# FPGA_board-v1.net
KiCad netlist of a schematic drawn in EAGLE
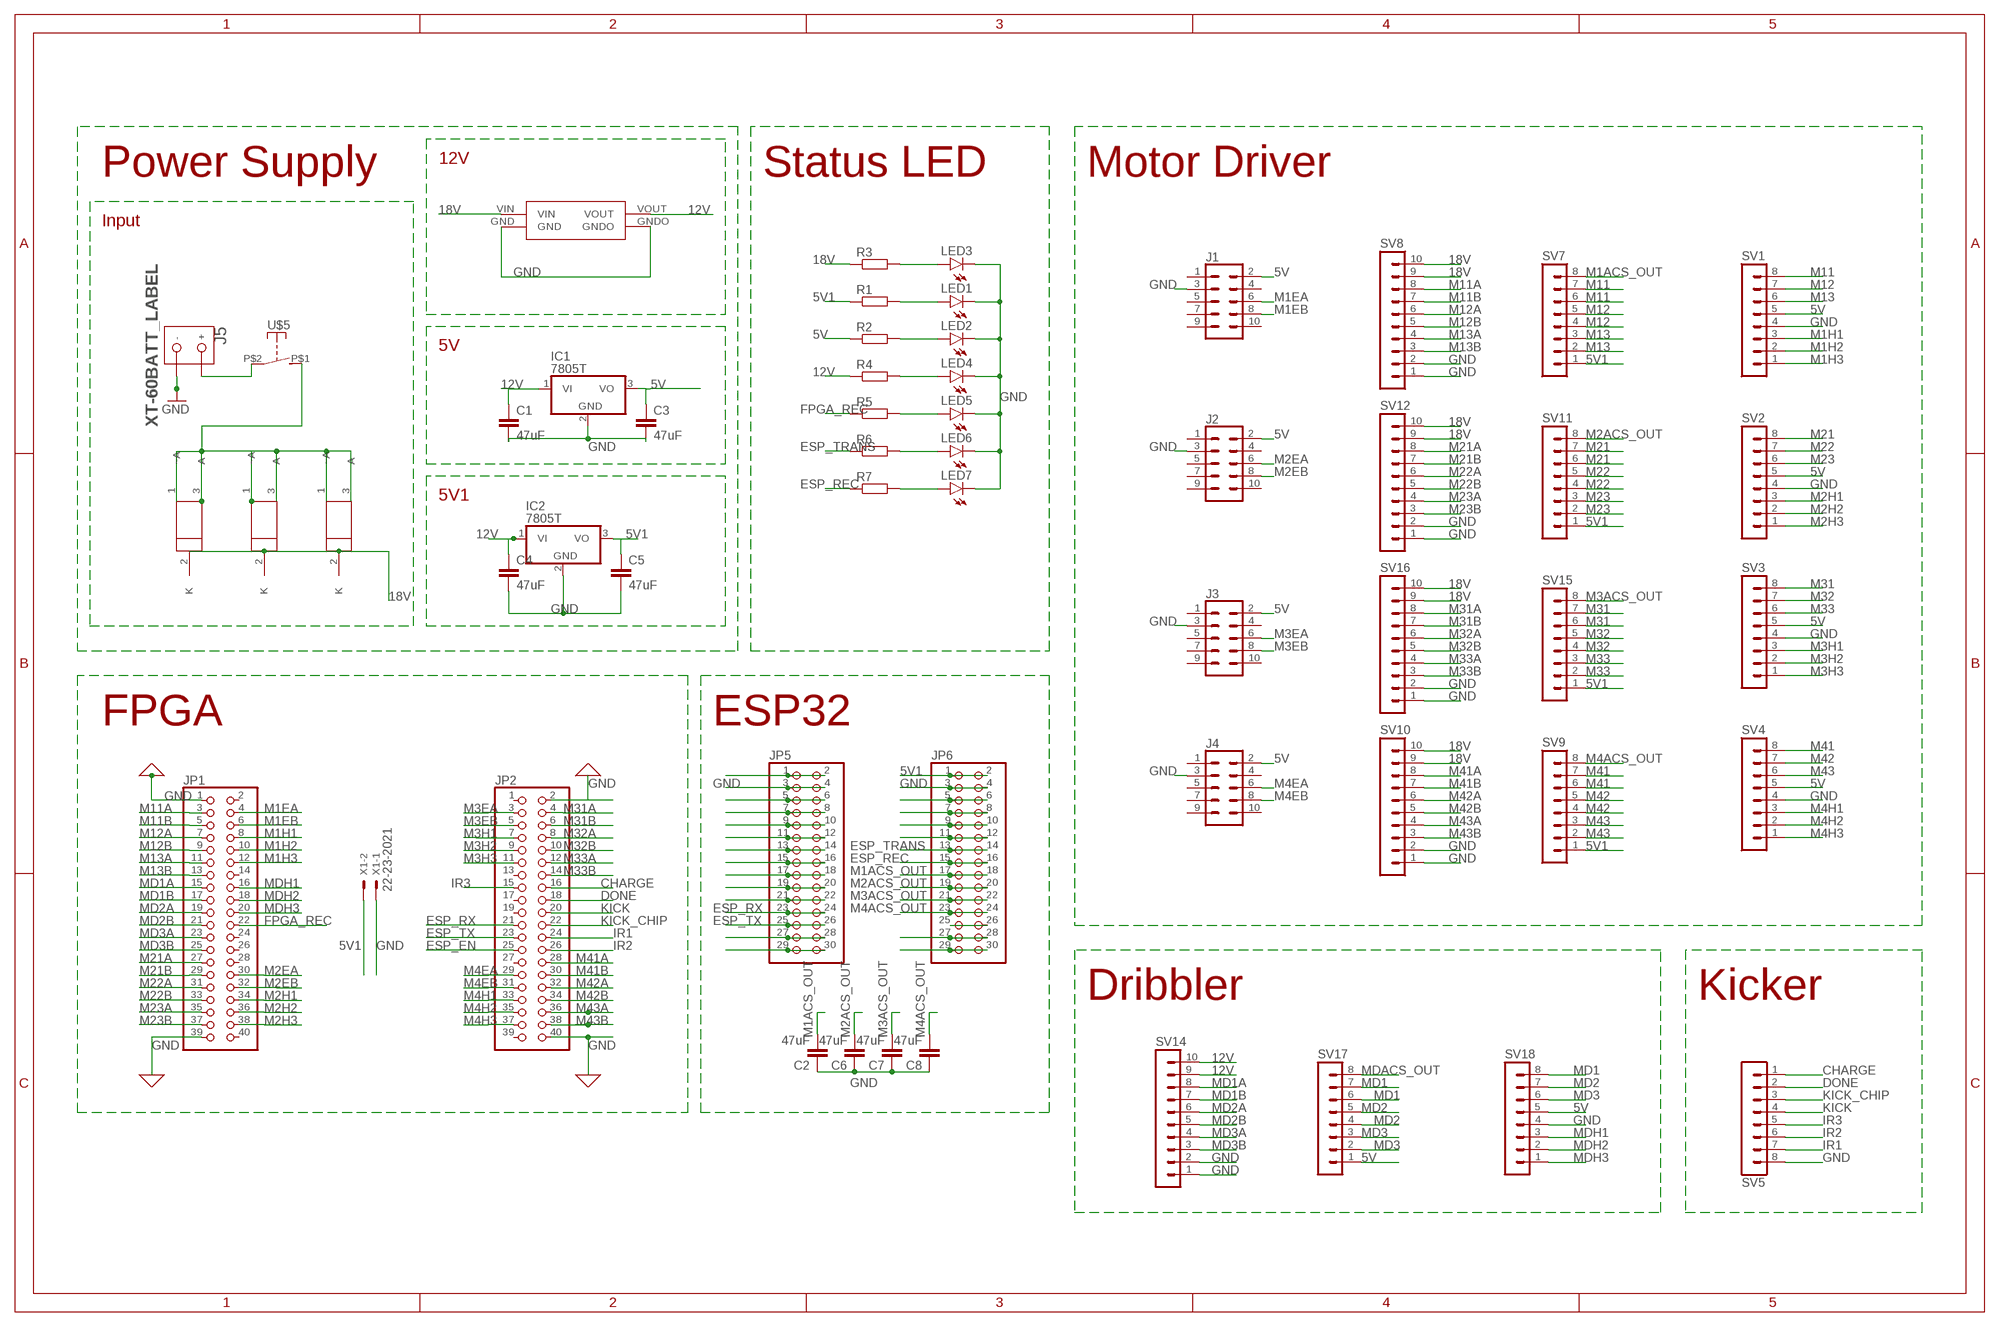
[diagram p0: schematic, sheet 1]

(export (version "E")
  (design (tool "Eeschema 10.0.6"))
  (components
    (comp (ref "C1")
      (value "47uF")
      (footprint "eagle-import:C1206")
      (libsource (lib "eagle-import") (part "C-EUC1206"))
    )
    (comp (ref "C2")
      (value "47uF")
      (footprint "eagle-import:C1206")
      (libsource (lib "eagle-import") (part "C-EUC1206"))
    )
    (comp (ref "C3")
      (value "47uF")
      (footprint "eagle-import:C1206")
      (libsource (lib "eagle-import") (part "C-EUC1206"))
    )
    (comp (ref "C4")
      (value "47uF")
      (footprint "eagle-import:C1206")
      (libsource (lib "eagle-import") (part "C-EUC1206"))
    )
    (comp (ref "C5")
      (value "47uF")
      (footprint "eagle-import:C1206")
      (libsource (lib "eagle-import") (part "C-EUC1206"))
    )
    (comp (ref "C6")
      (value "47uF")
      (footprint "eagle-import:C1206")
      (libsource (lib "eagle-import") (part "C-EUC1206"))
    )
    (comp (ref "C7")
      (value "47uF")
      (footprint "eagle-import:C1206")
      (libsource (lib "eagle-import") (part "C-EUC1206"))
    )
    (comp (ref "C8")
      (value "47uF")
      (footprint "eagle-import:C1206")
      (libsource (lib "eagle-import") (part "C-EUC1206"))
    )
    (comp (ref "IC1")
      (value "7805T")
      (footprint "eagle-import:TO220H")
      (libsource (lib "eagle-import") (part "78T05"))
    )
    (comp (ref "IC2")
      (value "7805T")
      (footprint "eagle-import:TO220H")
      (libsource (lib "eagle-import") (part "78T05"))
    )
    (comp (ref "J1")
      (value "CONN_05X2SHD_LOCK")
      (footprint "eagle-import:2X5-SHROUDED_LOCK")
      (libsource (lib "eagle-import") (part "CONN_05X2SHD_LOCK"))
    )
    (comp (ref "J2")
      (value "CONN_05X2SHD_LOCK")
      (footprint "eagle-import:2X5-SHROUDED_LOCK")
      (libsource (lib "eagle-import") (part "CONN_05X2SHD_LOCK"))
    )
    (comp (ref "J3")
      (value "CONN_05X2SHD_LOCK")
      (footprint "eagle-import:2X5-SHROUDED_LOCK")
      (libsource (lib "eagle-import") (part "CONN_05X2SHD_LOCK"))
    )
    (comp (ref "J4")
      (value "CONN_05X2SHD_LOCK")
      (footprint "eagle-import:2X5-SHROUDED_LOCK")
      (libsource (lib "eagle-import") (part "CONN_05X2SHD_LOCK"))
    )
    (comp (ref "J5")
      (value "XT-60BATT_LABEL")
      (footprint "eagle-import:XT-60")
      (libsource (lib "eagle-import") (part "XT-60BATT_LABEL"))
    )
    (comp (ref "JP1")
      (value "PINHD-2X20")
      (footprint "eagle-import:2X20")
      (libsource (lib "eagle-import") (part "PINHD-2X20"))
    )
    (comp (ref "JP2")
      (value "PINHD-2X20")
      (footprint "eagle-import:2X20")
      (libsource (lib "eagle-import") (part "PINHD-2X20"))
    )
    (comp (ref "JP5")
      (value "PINHD-2X15")
      (footprint "eagle-import:2X15")
      (libsource (lib "eagle-import") (part "PINHD-2X15"))
    )
    (comp (ref "JP6")
      (value "PINHD-2X15")
      (footprint "eagle-import:2X15")
      (libsource (lib "eagle-import") (part "PINHD-2X15"))
    )
    (comp (ref "LED1")
      (value "LEDSMT1206")
      (footprint "eagle-import:1206")
      (libsource (lib "eagle-import") (part "LEDSMT1206"))
    )
    (comp (ref "LED2")
      (value "LEDSMT1206")
      (footprint "eagle-import:1206")
      (libsource (lib "eagle-import") (part "LEDSMT1206"))
    )
    (comp (ref "LED3")
      (value "LEDSMT1206")
      (footprint "eagle-import:1206")
      (libsource (lib "eagle-import") (part "LEDSMT1206"))
    )
    (comp (ref "LED4")
      (value "LEDSMT1206")
      (footprint "eagle-import:1206")
      (libsource (lib "eagle-import") (part "LEDSMT1206"))
    )
    (comp (ref "LED5")
      (value "LEDSMT1206")
      (footprint "eagle-import:1206")
      (libsource (lib "eagle-import") (part "LEDSMT1206"))
    )
    (comp (ref "LED6")
      (value "LEDSMT1206")
      (footprint "eagle-import:1206")
      (libsource (lib "eagle-import") (part "LEDSMT1206"))
    )
    (comp (ref "LED7")
      (value "LEDSMT1206")
      (footprint "eagle-import:1206")
      (libsource (lib "eagle-import") (part "LEDSMT1206"))
    )
    (comp (ref "R1")
      (value "R-EU_R1206")
      (footprint "eagle-import:R1206")
      (libsource (lib "eagle-import") (part "R-EU_R1206"))
    )
    (comp (ref "R2")
      (value "R-EU_R1206")
      (footprint "eagle-import:R1206")
      (libsource (lib "eagle-import") (part "R-EU_R1206"))
    )
    (comp (ref "R3")
      (value "R-EU_R1206")
      (footprint "eagle-import:R1206")
      (libsource (lib "eagle-import") (part "R-EU_R1206"))
    )
    (comp (ref "R4")
      (value "R-EU_R1206")
      (footprint "eagle-import:R1206")
      (libsource (lib "eagle-import") (part "R-EU_R1206"))
    )
    (comp (ref "R5")
      (value "R-EU_R1206")
      (footprint "eagle-import:R1206")
      (libsource (lib "eagle-import") (part "R-EU_R1206"))
    )
    (comp (ref "R6")
      (value "R-EU_R1206")
      (footprint "eagle-import:R1206")
      (libsource (lib "eagle-import") (part "R-EU_R1206"))
    )
    (comp (ref "R7")
      (value "R-EU_R1206")
      (footprint "eagle-import:R1206")
      (libsource (lib "eagle-import") (part "R-EU_R1206"))
    )
    (comp (ref "SV1")
      (value "MA08-1")
      (footprint "eagle-import:MA08-1")
      (libsource (lib "eagle-import") (part "MA08-1"))
    )
    (comp (ref "SV2")
      (value "MA08-1")
      (footprint "eagle-import:MA08-1")
      (libsource (lib "eagle-import") (part "MA08-1"))
    )
    (comp (ref "SV3")
      (value "MA08-1")
      (footprint "eagle-import:MA08-1")
      (libsource (lib "eagle-import") (part "MA08-1"))
    )
    (comp (ref "SV4")
      (value "MA08-1")
      (footprint "eagle-import:MA08-1")
      (libsource (lib "eagle-import") (part "MA08-1"))
    )
    (comp (ref "SV5")
      (value "MA08-1")
      (footprint "eagle-import:MA08-1")
      (libsource (lib "eagle-import") (part "MA08-1"))
    )
    (comp (ref "SV7")
      (value "MA08-1")
      (footprint "eagle-import:MA08-1")
      (libsource (lib "eagle-import") (part "MA08-1"))
    )
    (comp (ref "SV8")
      (value "MA10-1")
      (footprint "eagle-import:MA10-1")
      (libsource (lib "eagle-import") (part "MA10-1"))
    )
    (comp (ref "SV9")
      (value "MA08-1")
      (footprint "eagle-import:MA08-1")
      (libsource (lib "eagle-import") (part "MA08-1"))
    )
    (comp (ref "SV10")
      (value "MA10-1")
      (footprint "eagle-import:MA10-1")
      (libsource (lib "eagle-import") (part "MA10-1"))
    )
    (comp (ref "SV11")
      (value "MA08-1")
      (footprint "eagle-import:MA08-1")
      (libsource (lib "eagle-import") (part "MA08-1"))
    )
    (comp (ref "SV12")
      (value "MA10-1")
      (footprint "eagle-import:MA10-1")
      (libsource (lib "eagle-import") (part "MA10-1"))
    )
    (comp (ref "SV14")
      (value "MA10-1")
      (footprint "eagle-import:MA10-1")
      (libsource (lib "eagle-import") (part "MA10-1"))
    )
    (comp (ref "SV15")
      (value "MA08-1")
      (footprint "eagle-import:MA08-1")
      (libsource (lib "eagle-import") (part "MA08-1"))
    )
    (comp (ref "SV16")
      (value "MA10-1")
      (footprint "eagle-import:MA10-1")
      (libsource (lib "eagle-import") (part "MA10-1"))
    )
    (comp (ref "SV17")
      (value "MA08-1")
      (footprint "eagle-import:MA08-1")
      (libsource (lib "eagle-import") (part "MA08-1"))
    )
    (comp (ref "SV18")
      (value "MA08-1")
      (footprint "eagle-import:MA08-1")
      (libsource (lib "eagle-import") (part "MA08-1"))
    )
    (comp (ref "U$4")
      (value "BUCK")
      (footprint "eagle-import:BUCK")
      (libsource (lib "eagle-import") (part "BUCK"))
    )
    (comp (ref "U$5")
      (value "SWITCH_DA10")
      (footprint "eagle-import:DA10")
      (libsource (lib "eagle-import") (part "SWITCH_DA10"))
    )
    (comp (ref "U1")
      (value "LP38690DT-3.3")
      (footprint "eagle-import:TO228P1042X238-3N")
      (libsource (lib "eagle-import") (part "LP38690DT-3.3"))
    )
    (comp (ref "U2")
      (value "LP38690DT-3.3")
      (footprint "eagle-import:TO228P1042X238-3N")
      (libsource (lib "eagle-import") (part "LP38690DT-3.3"))
    )
    (comp (ref "U3")
      (value "LP38690DT-3.3")
      (footprint "eagle-import:TO228P1042X238-3N")
      (libsource (lib "eagle-import") (part "LP38690DT-3.3"))
    )
    (comp (ref "X1")
      (value "22-23-2021")
      (footprint "eagle-import:22-23-2021")
      (fields (field (name "MF") "MOLEX"))
      (libsource (lib "eagle-import") (part "22-23-2021"))
    )
  )
  (nets
    (net (code "1") (name "/5V") (class "Default")
      (node (ref "C3") (pin "1") (pinfunction "1_1") (pintype "passive"))
      (node (ref "IC1") (pin "3") (pinfunction "VO_3") (pintype "passive"))
      (node (ref "J1") (pin "2") (pinfunction "2_2") (pintype "passive"))
      (node (ref "J2") (pin "2") (pinfunction "2_2") (pintype "passive"))
      (node (ref "J3") (pin "2") (pinfunction "2_2") (pintype "passive"))
      (node (ref "J4") (pin "2") (pinfunction "2_2") (pintype "passive"))
      (node (ref "R2") (pin "1") (pinfunction "1_1") (pintype "passive"))
      (node (ref "SV1") (pin "5") (pinfunction "5_5") (pintype "passive"))
      (node (ref "SV17") (pin "1") (pinfunction "1_1") (pintype "passive"))
      (node (ref "SV18") (pin "5") (pinfunction "5_5") (pintype "passive"))
      (node (ref "SV2") (pin "5") (pinfunction "5_5") (pintype "passive"))
      (node (ref "SV3") (pin "5") (pinfunction "5_5") (pintype "passive"))
      (node (ref "SV4") (pin "5") (pinfunction "5_5") (pintype "passive"))
    )
    (net (code "2") (name "/5V1") (class "Default")
      (node (ref "C5") (pin "1") (pinfunction "1_1") (pintype "passive"))
      (node (ref "IC2") (pin "3") (pinfunction "VO_3") (pintype "passive"))
      (node (ref "JP6") (pin "1") (pinfunction "1_1") (pintype "passive"))
      (node (ref "JP6") (pin "2") (pinfunction "2_2") (pintype "passive"))
      (node (ref "R1") (pin "1") (pinfunction "1_1") (pintype "passive"))
      (node (ref "SV11") (pin "1") (pinfunction "1_1") (pintype "passive"))
      (node (ref "SV15") (pin "1") (pinfunction "1_1") (pintype "passive"))
      (node (ref "SV7") (pin "1") (pinfunction "1_1") (pintype "passive"))
      (node (ref "SV9") (pin "1") (pinfunction "1_1") (pintype "passive"))
      (node (ref "X1") (pin "2") (pinfunction "S_2") (pintype "passive"))
    )
    (net (code "3") (name "/12V") (class "Default")
      (node (ref "C1") (pin "1") (pinfunction "1_1") (pintype "passive"))
      (node (ref "C4") (pin "1") (pinfunction "1_1") (pintype "passive"))
      (node (ref "IC1") (pin "1") (pinfunction "VI_1") (pintype "input"))
      (node (ref "IC2") (pin "1") (pinfunction "VI_1") (pintype "input"))
      (node (ref "R4") (pin "1") (pinfunction "1_1") (pintype "passive"))
      (node (ref "SV14") (pin "10") (pinfunction "10_10") (pintype "passive"))
      (node (ref "SV14") (pin "9") (pinfunction "9_9") (pintype "passive"))
      (node (ref "U$4") (pin "VOUT") (pinfunction "VOUT_VOUT") (pintype "bidirectional"))
    )
    (net (code "4") (name "/18V") (class "Default")
      (node (ref "R3") (pin "1") (pinfunction "1_1") (pintype "passive"))
      (node (ref "SV10") (pin "10") (pinfunction "10_10") (pintype "passive"))
      (node (ref "SV10") (pin "9") (pinfunction "9_9") (pintype "passive"))
      (node (ref "SV12") (pin "10") (pinfunction "10_10") (pintype "passive"))
      (node (ref "SV12") (pin "9") (pinfunction "9_9") (pintype "passive"))
      (node (ref "SV16") (pin "10") (pinfunction "10_10") (pintype "passive"))
      (node (ref "SV16") (pin "9") (pinfunction "9_9") (pintype "passive"))
      (node (ref "SV8") (pin "10") (pinfunction "10_10") (pintype "passive"))
      (node (ref "SV8") (pin "9") (pinfunction "9_9") (pintype "passive"))
      (node (ref "U$4") (pin "VIN") (pinfunction "VIN_VIN") (pintype "bidirectional"))
      (node (ref "U1") (pin "2") (pinfunction "K_2") (pintype "bidirectional"))
      (node (ref "U2") (pin "2") (pinfunction "K_2") (pintype "bidirectional"))
      (node (ref "U3") (pin "2") (pinfunction "K_2") (pintype "bidirectional"))
    )
    (net (code "5") (name "/CHARGE") (class "Default")
      (node (ref "JP2") (pin "16") (pinfunction "16_16") (pintype "passive"))
      (node (ref "SV5") (pin "1") (pinfunction "1_1") (pintype "passive"))
    )
    (net (code "6") (name "/DONE") (class "Default")
      (node (ref "JP2") (pin "18") (pinfunction "18_18") (pintype "passive"))
      (node (ref "SV5") (pin "2") (pinfunction "2_2") (pintype "passive"))
    )
    (net (code "7") (name "/ESP_EN") (class "Default")
      (node (ref "JP2") (pin "25") (pinfunction "25_25") (pintype "passive"))
    )
    (net (code "8") (name "/ESP_REC") (class "Default")
      (node (ref "JP6") (pin "15") (pinfunction "15_15") (pintype "passive"))
      (node (ref "JP6") (pin "16") (pinfunction "16_16") (pintype "passive"))
      (node (ref "R7") (pin "1") (pinfunction "1_1") (pintype "passive"))
    )
    (net (code "9") (name "/ESP_RX") (class "Default")
      (node (ref "JP2") (pin "21") (pinfunction "21_21") (pintype "passive"))
      (node (ref "JP5") (pin "23") (pinfunction "23_23") (pintype "passive"))
      (node (ref "JP5") (pin "24") (pinfunction "24_24") (pintype "passive"))
    )
    (net (code "10") (name "/ESP_TRANS") (class "Default")
      (node (ref "JP6") (pin "13") (pinfunction "13_13") (pintype "passive"))
      (node (ref "JP6") (pin "14") (pinfunction "14_14") (pintype "passive"))
      (node (ref "R6") (pin "1") (pinfunction "1_1") (pintype "passive"))
    )
    (net (code "11") (name "/ESP_TX") (class "Default")
      (node (ref "JP2") (pin "23") (pinfunction "23_23") (pintype "passive"))
      (node (ref "JP5") (pin "25") (pinfunction "25_25") (pintype "passive"))
      (node (ref "JP5") (pin "26") (pinfunction "26_26") (pintype "passive"))
    )
    (net (code "12") (name "/FPGA_REC") (class "Default")
      (node (ref "JP1") (pin "22") (pinfunction "22_22") (pintype "passive"))
      (node (ref "R5") (pin "1") (pinfunction "1_1") (pintype "passive"))
    )
    (net (code "13") (name "/IR1") (class "Default")
      (node (ref "JP2") (pin "24") (pinfunction "24_24") (pintype "passive"))
      (node (ref "SV5") (pin "7") (pinfunction "7_7") (pintype "passive"))
    )
    (net (code "14") (name "/IR2") (class "Default")
      (node (ref "JP2") (pin "26") (pinfunction "26_26") (pintype "passive"))
      (node (ref "SV5") (pin "6") (pinfunction "6_6") (pintype "passive"))
    )
    (net (code "15") (name "/IR3") (class "Default")
      (node (ref "JP2") (pin "15") (pinfunction "15_15") (pintype "passive"))
      (node (ref "SV5") (pin "5") (pinfunction "5_5") (pintype "passive"))
    )
    (net (code "16") (name "/KICK") (class "Default")
      (node (ref "JP2") (pin "20") (pinfunction "20_20") (pintype "passive"))
      (node (ref "SV5") (pin "4") (pinfunction "4_4") (pintype "passive"))
    )
    (net (code "17") (name "/KICK_CHIP") (class "Default")
      (node (ref "JP2") (pin "22") (pinfunction "22_22") (pintype "passive"))
      (node (ref "SV5") (pin "3") (pinfunction "3_3") (pintype "passive"))
    )
    (net (code "18") (name "/M1ACS_OUT") (class "Default")
      (node (ref "C2") (pin "2") (pinfunction "2_2") (pintype "passive"))
      (node (ref "JP6") (pin "17") (pinfunction "17_17") (pintype "passive"))
      (node (ref "JP6") (pin "18") (pinfunction "18_18") (pintype "passive"))
      (node (ref "SV7") (pin "8") (pinfunction "8_8") (pintype "passive"))
    )
    (net (code "19") (name "/M1EA") (class "Default")
      (node (ref "J1") (pin "6") (pinfunction "6_6") (pintype "passive"))
      (node (ref "JP1") (pin "4") (pinfunction "4_4") (pintype "passive"))
    )
    (net (code "20") (name "/M1EB") (class "Default")
      (node (ref "J1") (pin "8") (pinfunction "8_8") (pintype "passive"))
      (node (ref "JP1") (pin "6") (pinfunction "6_6") (pintype "passive"))
    )
    (net (code "21") (name "/M1H1") (class "Default")
      (node (ref "JP1") (pin "8") (pinfunction "8_8") (pintype "passive"))
      (node (ref "SV1") (pin "3") (pinfunction "3_3") (pintype "passive"))
    )
    (net (code "22") (name "/M1H2") (class "Default")
      (node (ref "JP1") (pin "10") (pinfunction "10_10") (pintype "passive"))
      (node (ref "SV1") (pin "2") (pinfunction "2_2") (pintype "passive"))
    )
    (net (code "23") (name "/M1H3") (class "Default")
      (node (ref "JP1") (pin "12") (pinfunction "12_12") (pintype "passive"))
      (node (ref "SV1") (pin "1") (pinfunction "1_1") (pintype "passive"))
    )
    (net (code "24") (name "/M2ACS_OUT") (class "Default")
      (node (ref "C6") (pin "2") (pinfunction "2_2") (pintype "passive"))
      (node (ref "JP6") (pin "19") (pinfunction "19_19") (pintype "passive"))
      (node (ref "JP6") (pin "20") (pinfunction "20_20") (pintype "passive"))
      (node (ref "SV11") (pin "8") (pinfunction "8_8") (pintype "passive"))
    )
    (net (code "25") (name "/M2EA") (class "Default")
      (node (ref "J2") (pin "6") (pinfunction "6_6") (pintype "passive"))
      (node (ref "JP1") (pin "30") (pinfunction "30_30") (pintype "passive"))
    )
    (net (code "26") (name "/M2EB") (class "Default")
      (node (ref "J2") (pin "8") (pinfunction "8_8") (pintype "passive"))
      (node (ref "JP1") (pin "32") (pinfunction "32_32") (pintype "passive"))
    )
    (net (code "27") (name "/M2H1") (class "Default")
      (node (ref "JP1") (pin "34") (pinfunction "34_34") (pintype "passive"))
      (node (ref "SV2") (pin "3") (pinfunction "3_3") (pintype "passive"))
    )
    (net (code "28") (name "/M2H2") (class "Default")
      (node (ref "JP1") (pin "36") (pinfunction "36_36") (pintype "passive"))
      (node (ref "SV2") (pin "2") (pinfunction "2_2") (pintype "passive"))
    )
    (net (code "29") (name "/M2H3") (class "Default")
      (node (ref "JP1") (pin "38") (pinfunction "38_38") (pintype "passive"))
      (node (ref "SV2") (pin "1") (pinfunction "1_1") (pintype "passive"))
    )
    (net (code "30") (name "/M3ACS_OUT") (class "Default")
      (node (ref "C7") (pin "2") (pinfunction "2_2") (pintype "passive"))
      (node (ref "JP6") (pin "21") (pinfunction "21_21") (pintype "passive"))
      (node (ref "JP6") (pin "22") (pinfunction "22_22") (pintype "passive"))
      (node (ref "SV15") (pin "8") (pinfunction "8_8") (pintype "passive"))
    )
    (net (code "31") (name "/M3EA") (class "Default")
      (node (ref "J3") (pin "6") (pinfunction "6_6") (pintype "passive"))
      (node (ref "JP2") (pin "3") (pinfunction "3_3") (pintype "passive"))
    )
    (net (code "32") (name "/M3EB") (class "Default")
      (node (ref "J3") (pin "8") (pinfunction "8_8") (pintype "passive"))
      (node (ref "JP2") (pin "5") (pinfunction "5_5") (pintype "passive"))
    )
    (net (code "33") (name "/M3H1") (class "Default")
      (node (ref "JP2") (pin "7") (pinfunction "7_7") (pintype "passive"))
      (node (ref "SV3") (pin "3") (pinfunction "3_3") (pintype "passive"))
    )
    (net (code "34") (name "/M3H2") (class "Default")
      (node (ref "JP2") (pin "9") (pinfunction "9_9") (pintype "passive"))
      (node (ref "SV3") (pin "2") (pinfunction "2_2") (pintype "passive"))
    )
    (net (code "35") (name "/M3H3") (class "Default")
      (node (ref "JP2") (pin "11") (pinfunction "11_11") (pintype "passive"))
      (node (ref "SV3") (pin "1") (pinfunction "1_1") (pintype "passive"))
    )
    (net (code "36") (name "/M4ACS_OUT") (class "Default")
      (node (ref "C8") (pin "2") (pinfunction "2_2") (pintype "passive"))
      (node (ref "JP6") (pin "23") (pinfunction "23_23") (pintype "passive"))
      (node (ref "JP6") (pin "24") (pinfunction "24_24") (pintype "passive"))
      (node (ref "SV9") (pin "8") (pinfunction "8_8") (pintype "passive"))
    )
    (net (code "37") (name "/M4EA") (class "Default")
      (node (ref "J4") (pin "6") (pinfunction "6_6") (pintype "passive"))
      (node (ref "JP2") (pin "29") (pinfunction "29_29") (pintype "passive"))
    )
    (net (code "38") (name "/M4EB") (class "Default")
      (node (ref "J4") (pin "8") (pinfunction "8_8") (pintype "passive"))
      (node (ref "JP2") (pin "31") (pinfunction "31_31") (pintype "passive"))
    )
    (net (code "39") (name "/M4H1") (class "Default")
      (node (ref "JP2") (pin "33") (pinfunction "33_33") (pintype "passive"))
      (node (ref "SV4") (pin "3") (pinfunction "3_3") (pintype "passive"))
    )
    (net (code "40") (name "/M4H2") (class "Default")
      (node (ref "JP2") (pin "35") (pinfunction "35_35") (pintype "passive"))
      (node (ref "SV4") (pin "2") (pinfunction "2_2") (pintype "passive"))
    )
    (net (code "41") (name "/M4H3") (class "Default")
      (node (ref "JP2") (pin "37") (pinfunction "37_37") (pintype "passive"))
      (node (ref "SV4") (pin "1") (pinfunction "1_1") (pintype "passive"))
    )
    (net (code "42") (name "/M11") (class "Default")
      (node (ref "SV1") (pin "8") (pinfunction "8_8") (pintype "passive"))
      (node (ref "SV7") (pin "6") (pinfunction "6_6") (pintype "passive"))
      (node (ref "SV7") (pin "7") (pinfunction "7_7") (pintype "passive"))
    )
    (net (code "43") (name "/M11A") (class "Default")
      (node (ref "JP1") (pin "3") (pinfunction "3_3") (pintype "passive"))
      (node (ref "SV8") (pin "8") (pinfunction "8_8") (pintype "passive"))
    )
    (net (code "44") (name "/M11B") (class "Default")
      (node (ref "JP1") (pin "5") (pinfunction "5_5") (pintype "passive"))
      (node (ref "SV8") (pin "7") (pinfunction "7_7") (pintype "passive"))
    )
    (net (code "45") (name "/M12") (class "Default")
      (node (ref "SV1") (pin "7") (pinfunction "7_7") (pintype "passive"))
      (node (ref "SV7") (pin "4") (pinfunction "4_4") (pintype "passive"))
      (node (ref "SV7") (pin "5") (pinfunction "5_5") (pintype "passive"))
    )
    (net (code "46") (name "/M12A") (class "Default")
      (node (ref "JP1") (pin "7") (pinfunction "7_7") (pintype "passive"))
      (node (ref "SV8") (pin "6") (pinfunction "6_6") (pintype "passive"))
    )
    (net (code "47") (name "/M12B") (class "Default")
      (node (ref "JP1") (pin "9") (pinfunction "9_9") (pintype "passive"))
      (node (ref "SV8") (pin "5") (pinfunction "5_5") (pintype "passive"))
    )
    (net (code "48") (name "/M13") (class "Default")
      (node (ref "SV1") (pin "6") (pinfunction "6_6") (pintype "passive"))
      (node (ref "SV7") (pin "2") (pinfunction "2_2") (pintype "passive"))
      (node (ref "SV7") (pin "3") (pinfunction "3_3") (pintype "passive"))
    )
    (net (code "49") (name "/M13A") (class "Default")
      (node (ref "JP1") (pin "11") (pinfunction "11_11") (pintype "passive"))
      (node (ref "SV8") (pin "4") (pinfunction "4_4") (pintype "passive"))
    )
    (net (code "50") (name "/M13B") (class "Default")
      (node (ref "JP1") (pin "13") (pinfunction "13_13") (pintype "passive"))
      (node (ref "SV8") (pin "3") (pinfunction "3_3") (pintype "passive"))
    )
    (net (code "51") (name "/M21") (class "Default")
      (node (ref "SV11") (pin "6") (pinfunction "6_6") (pintype "passive"))
      (node (ref "SV11") (pin "7") (pinfunction "7_7") (pintype "passive"))
      (node (ref "SV2") (pin "8") (pinfunction "8_8") (pintype "passive"))
    )
    (net (code "52") (name "/M21A") (class "Default")
      (node (ref "JP1") (pin "27") (pinfunction "27_27") (pintype "passive"))
      (node (ref "SV12") (pin "8") (pinfunction "8_8") (pintype "passive"))
    )
    (net (code "53") (name "/M21B") (class "Default")
      (node (ref "JP1") (pin "29") (pinfunction "29_29") (pintype "passive"))
      (node (ref "SV12") (pin "7") (pinfunction "7_7") (pintype "passive"))
    )
    (net (code "54") (name "/M22") (class "Default")
      (node (ref "SV11") (pin "4") (pinfunction "4_4") (pintype "passive"))
      (node (ref "SV11") (pin "5") (pinfunction "5_5") (pintype "passive"))
      (node (ref "SV2") (pin "7") (pinfunction "7_7") (pintype "passive"))
    )
    (net (code "55") (name "/M22A") (class "Default")
      (node (ref "JP1") (pin "31") (pinfunction "31_31") (pintype "passive"))
      (node (ref "SV12") (pin "6") (pinfunction "6_6") (pintype "passive"))
    )
    (net (code "56") (name "/M22B") (class "Default")
      (node (ref "JP1") (pin "33") (pinfunction "33_33") (pintype "passive"))
      (node (ref "SV12") (pin "5") (pinfunction "5_5") (pintype "passive"))
    )
    (net (code "57") (name "/M23") (class "Default")
      (node (ref "SV11") (pin "2") (pinfunction "2_2") (pintype "passive"))
      (node (ref "SV11") (pin "3") (pinfunction "3_3") (pintype "passive"))
      (node (ref "SV2") (pin "6") (pinfunction "6_6") (pintype "passive"))
    )
    (net (code "58") (name "/M23A") (class "Default")
      (node (ref "JP1") (pin "35") (pinfunction "35_35") (pintype "passive"))
      (node (ref "SV12") (pin "4") (pinfunction "4_4") (pintype "passive"))
    )
    (net (code "59") (name "/M23B") (class "Default")
      (node (ref "JP1") (pin "37") (pinfunction "37_37") (pintype "passive"))
      (node (ref "SV12") (pin "3") (pinfunction "3_3") (pintype "passive"))
    )
    (net (code "60") (name "/M31") (class "Default")
      (node (ref "SV15") (pin "6") (pinfunction "6_6") (pintype "passive"))
      (node (ref "SV15") (pin "7") (pinfunction "7_7") (pintype "passive"))
      (node (ref "SV3") (pin "8") (pinfunction "8_8") (pintype "passive"))
    )
    (net (code "61") (name "/M31A") (class "Default")
      (node (ref "JP2") (pin "4") (pinfunction "4_4") (pintype "passive"))
      (node (ref "SV16") (pin "8") (pinfunction "8_8") (pintype "passive"))
    )
    (net (code "62") (name "/M31B") (class "Default")
      (node (ref "JP2") (pin "6") (pinfunction "6_6") (pintype "passive"))
      (node (ref "SV16") (pin "7") (pinfunction "7_7") (pintype "passive"))
    )
    (net (code "63") (name "/M32") (class "Default")
      (node (ref "SV15") (pin "4") (pinfunction "4_4") (pintype "passive"))
      (node (ref "SV15") (pin "5") (pinfunction "5_5") (pintype "passive"))
      (node (ref "SV3") (pin "7") (pinfunction "7_7") (pintype "passive"))
    )
    (net (code "64") (name "/M32A") (class "Default")
      (node (ref "JP2") (pin "8") (pinfunction "8_8") (pintype "passive"))
      (node (ref "SV16") (pin "6") (pinfunction "6_6") (pintype "passive"))
    )
    (net (code "65") (name "/M32B") (class "Default")
      (node (ref "JP2") (pin "10") (pinfunction "10_10") (pintype "passive"))
      (node (ref "SV16") (pin "5") (pinfunction "5_5") (pintype "passive"))
    )
    (net (code "66") (name "/M33") (class "Default")
      (node (ref "SV15") (pin "2") (pinfunction "2_2") (pintype "passive"))
      (node (ref "SV15") (pin "3") (pinfunction "3_3") (pintype "passive"))
      (node (ref "SV3") (pin "6") (pinfunction "6_6") (pintype "passive"))
    )
    (net (code "67") (name "/M33A") (class "Default")
      (node (ref "JP2") (pin "12") (pinfunction "12_12") (pintype "passive"))
      (node (ref "SV16") (pin "4") (pinfunction "4_4") (pintype "passive"))
    )
    (net (code "68") (name "/M33B") (class "Default")
      (node (ref "JP2") (pin "14") (pinfunction "14_14") (pintype "passive"))
      (node (ref "SV16") (pin "3") (pinfunction "3_3") (pintype "passive"))
    )
    (net (code "69") (name "/M41") (class "Default")
      (node (ref "SV4") (pin "8") (pinfunction "8_8") (pintype "passive"))
      (node (ref "SV9") (pin "6") (pinfunction "6_6") (pintype "passive"))
      (node (ref "SV9") (pin "7") (pinfunction "7_7") (pintype "passive"))
    )
    (net (code "70") (name "/M41A") (class "Default")
      (node (ref "JP2") (pin "28") (pinfunction "28_28") (pintype "passive"))
      (node (ref "SV10") (pin "8") (pinfunction "8_8") (pintype "passive"))
    )
    (net (code "71") (name "/M41B") (class "Default")
      (node (ref "JP2") (pin "30") (pinfunction "30_30") (pintype "passive"))
      (node (ref "SV10") (pin "7") (pinfunction "7_7") (pintype "passive"))
    )
    (net (code "72") (name "/M42") (class "Default")
      (node (ref "SV4") (pin "7") (pinfunction "7_7") (pintype "passive"))
      (node (ref "SV9") (pin "4") (pinfunction "4_4") (pintype "passive"))
      (node (ref "SV9") (pin "5") (pinfunction "5_5") (pintype "passive"))
    )
    (net (code "73") (name "/M42A") (class "Default")
      (node (ref "JP2") (pin "32") (pinfunction "32_32") (pintype "passive"))
      (node (ref "SV10") (pin "6") (pinfunction "6_6") (pintype "passive"))
    )
    (net (code "74") (name "/M42B") (class "Default")
      (node (ref "JP2") (pin "34") (pinfunction "34_34") (pintype "passive"))
      (node (ref "SV10") (pin "5") (pinfunction "5_5") (pintype "passive"))
    )
    (net (code "75") (name "/M43") (class "Default")
      (node (ref "SV4") (pin "6") (pinfunction "6_6") (pintype "passive"))
      (node (ref "SV9") (pin "2") (pinfunction "2_2") (pintype "passive"))
      (node (ref "SV9") (pin "3") (pinfunction "3_3") (pintype "passive"))
    )
    (net (code "76") (name "/M43A") (class "Default")
      (node (ref "JP2") (pin "36") (pinfunction "36_36") (pintype "passive"))
      (node (ref "SV10") (pin "4") (pinfunction "4_4") (pintype "passive"))
    )
    (net (code "77") (name "/M43B") (class "Default")
      (node (ref "JP2") (pin "38") (pinfunction "38_38") (pintype "passive"))
      (node (ref "SV10") (pin "3") (pinfunction "3_3") (pintype "passive"))
    )
    (net (code "78") (name "/MD1") (class "Default")
      (node (ref "SV17") (pin "6") (pinfunction "6_6") (pintype "passive"))
      (node (ref "SV17") (pin "7") (pinfunction "7_7") (pintype "passive"))
      (node (ref "SV18") (pin "8") (pinfunction "8_8") (pintype "passive"))
    )
    (net (code "79") (name "/MD1A") (class "Default")
      (node (ref "JP1") (pin "15") (pinfunction "15_15") (pintype "passive"))
      (node (ref "SV14") (pin "8") (pinfunction "8_8") (pintype "passive"))
    )
    (net (code "80") (name "/MD1B") (class "Default")
      (node (ref "JP1") (pin "17") (pinfunction "17_17") (pintype "passive"))
      (node (ref "SV14") (pin "7") (pinfunction "7_7") (pintype "passive"))
    )
    (net (code "81") (name "/MD2") (class "Default")
      (node (ref "SV17") (pin "4") (pinfunction "4_4") (pintype "passive"))
      (node (ref "SV17") (pin "5") (pinfunction "5_5") (pintype "passive"))
      (node (ref "SV18") (pin "7") (pinfunction "7_7") (pintype "passive"))
    )
    (net (code "82") (name "/MD2A") (class "Default")
      (node (ref "JP1") (pin "19") (pinfunction "19_19") (pintype "passive"))
      (node (ref "SV14") (pin "6") (pinfunction "6_6") (pintype "passive"))
    )
    (net (code "83") (name "/MD2B") (class "Default")
      (node (ref "JP1") (pin "21") (pinfunction "21_21") (pintype "passive"))
      (node (ref "SV14") (pin "5") (pinfunction "5_5") (pintype "passive"))
    )
    (net (code "84") (name "/MD3") (class "Default")
      (node (ref "SV17") (pin "2") (pinfunction "2_2") (pintype "passive"))
      (node (ref "SV17") (pin "3") (pinfunction "3_3") (pintype "passive"))
      (node (ref "SV18") (pin "6") (pinfunction "6_6") (pintype "passive"))
    )
    (net (code "85") (name "/MD3A") (class "Default")
      (node (ref "JP1") (pin "23") (pinfunction "23_23") (pintype "passive"))
      (node (ref "SV14") (pin "4") (pinfunction "4_4") (pintype "passive"))
    )
    (net (code "86") (name "/MD3B") (class "Default")
      (node (ref "JP1") (pin "25") (pinfunction "25_25") (pintype "passive"))
      (node (ref "SV14") (pin "3") (pinfunction "3_3") (pintype "passive"))
    )
    (net (code "87") (name "/MDACS_OUT") (class "Default")
      (node (ref "SV17") (pin "8") (pinfunction "8_8") (pintype "passive"))
    )
    (net (code "88") (name "/MDH1") (class "Default")
      (node (ref "JP1") (pin "16") (pinfunction "16_16") (pintype "passive"))
      (node (ref "SV18") (pin "3") (pinfunction "3_3") (pintype "passive"))
    )
    (net (code "89") (name "/MDH2") (class "Default")
      (node (ref "JP1") (pin "18") (pinfunction "18_18") (pintype "passive"))
      (node (ref "SV18") (pin "2") (pinfunction "2_2") (pintype "passive"))
    )
    (net (code "90") (name "/MDH3") (class "Default")
      (node (ref "JP1") (pin "20") (pinfunction "20_20") (pintype "passive"))
      (node (ref "SV18") (pin "1") (pinfunction "1_1") (pintype "passive"))
    )
    (net (code "91") (name "GND") (class "Default")
      (node (ref "C1") (pin "2") (pinfunction "2_2") (pintype "passive"))
      (node (ref "C2") (pin "1") (pinfunction "1_1") (pintype "passive"))
      (node (ref "C3") (pin "2") (pinfunction "2_2") (pintype "passive"))
      (node (ref "C4") (pin "2") (pinfunction "2_2") (pintype "passive"))
      (node (ref "C5") (pin "2") (pinfunction "2_2") (pintype "passive"))
      (node (ref "C6") (pin "1") (pinfunction "1_1") (pintype "passive"))
      (node (ref "C7") (pin "1") (pinfunction "1_1") (pintype "passive"))
      (node (ref "C8") (pin "1") (pinfunction "1_1") (pintype "passive"))
      (node (ref "IC1") (pin "2") (pinfunction "GND_2") (pintype "passive"))
      (node (ref "IC2") (pin "2") (pinfunction "GND_2") (pintype "passive"))
      (node (ref "J1") (pin "3") (pinfunction "3_3") (pintype "passive"))
      (node (ref "J2") (pin "3") (pinfunction "3_3") (pintype "passive"))
      (node (ref "J3") (pin "3") (pinfunction "3_3") (pintype "passive"))
      (node (ref "J4") (pin "3") (pinfunction "3_3") (pintype "passive"))
      (node (ref "J5") (pin "GND") (pinfunction "-_GND") (pintype "passive"))
      (node (ref "JP1") (pin "1") (pinfunction "1_1") (pintype "passive"))
      (node (ref "JP1") (pin "39") (pinfunction "39_39") (pintype "passive"))
      (node (ref "JP2") (pin "2") (pinfunction "2_2") (pintype "passive"))
      (node (ref "JP2") (pin "40") (pinfunction "40_40") (pintype "passive"))
      (node (ref "JP5") (pin "3") (pinfunction "3_3") (pintype "passive"))
      (node (ref "JP5") (pin "4") (pinfunction "4_4") (pintype "passive"))
      (node (ref "JP6") (pin "3") (pinfunction "3_3") (pintype "passive"))
      (node (ref "JP6") (pin "4") (pinfunction "4_4") (pintype "passive"))
      (node (ref "LED1") (pin "C") (pinfunction "C_C") (pintype "passive"))
      (node (ref "LED2") (pin "C") (pinfunction "C_C") (pintype "passive"))
      (node (ref "LED3") (pin "C") (pinfunction "C_C") (pintype "passive"))
      (node (ref "LED4") (pin "C") (pinfunction "C_C") (pintype "passive"))
      (node (ref "LED5") (pin "C") (pinfunction "C_C") (pintype "passive"))
      (node (ref "LED6") (pin "C") (pinfunction "C_C") (pintype "passive"))
      (node (ref "LED7") (pin "C") (pinfunction "C_C") (pintype "passive"))
      (node (ref "SV1") (pin "4") (pinfunction "4_4") (pintype "passive"))
      (node (ref "SV10") (pin "1") (pinfunction "1_1") (pintype "passive"))
      (node (ref "SV10") (pin "2") (pinfunction "2_2") (pintype "passive"))
      (node (ref "SV12") (pin "1") (pinfunction "1_1") (pintype "passive"))
      (node (ref "SV12") (pin "2") (pinfunction "2_2") (pintype "passive"))
      (node (ref "SV14") (pin "1") (pinfunction "1_1") (pintype "passive"))
      (node (ref "SV14") (pin "2") (pinfunction "2_2") (pintype "passive"))
      (node (ref "SV16") (pin "1") (pinfunction "1_1") (pintype "passive"))
      (node (ref "SV16") (pin "2") (pinfunction "2_2") (pintype "passive"))
      (node (ref "SV18") (pin "4") (pinfunction "4_4") (pintype "passive"))
      (node (ref "SV2") (pin "4") (pinfunction "4_4") (pintype "passive"))
      (node (ref "SV3") (pin "4") (pinfunction "4_4") (pintype "passive"))
      (node (ref "SV4") (pin "4") (pinfunction "4_4") (pintype "passive"))
      (node (ref "SV5") (pin "8") (pinfunction "8_8") (pintype "passive"))
      (node (ref "SV8") (pin "1") (pinfunction "1_1") (pintype "passive"))
      (node (ref "SV8") (pin "2") (pinfunction "2_2") (pintype "passive"))
      (node (ref "U$4") (pin "GND") (pinfunction "GND_GND") (pintype "bidirectional"))
      (node (ref "U$4") (pin "GNDO") (pinfunction "GNDO_GNDO") (pintype "bidirectional"))
      (node (ref "X1") (pin "1") (pinfunction "S_1") (pintype "passive"))
    )
    (net (code "92") (name "Net-(J5-+)") (class "Default")
      (node (ref "J5") (pin "BATT") (pinfunction "+_BATT") (pintype "passive"))
      (node (ref "U$5") (pin "P$2") (pinfunction "P_P$2") (pintype "passive"))
    )
    (net (code "93") (name "Net-(JP5-Pad1)") (class "Default")
      (node (ref "JP5") (pin "1") (pinfunction "1_1") (pintype "passive"))
      (node (ref "JP5") (pin "2") (pinfunction "2_2") (pintype "passive"))
    )
    (net (code "94") (name "Net-(JP5-Pad5)") (class "Default")
      (node (ref "JP5") (pin "5") (pinfunction "5_5") (pintype "passive"))
      (node (ref "JP5") (pin "6") (pinfunction "6_6") (pintype "passive"))
    )
    (net (code "95") (name "Net-(JP5-Pad7)") (class "Default")
      (node (ref "JP5") (pin "7") (pinfunction "7_7") (pintype "passive"))
      (node (ref "JP5") (pin "8") (pinfunction "8_8") (pintype "passive"))
    )
    (net (code "96") (name "Net-(JP5-Pad10)") (class "Default")
      (node (ref "JP5") (pin "10") (pinfunction "10_10") (pintype "passive"))
      (node (ref "JP5") (pin "9") (pinfunction "9_9") (pintype "passive"))
    )
    (net (code "97") (name "Net-(JP5-Pad11)") (class "Default")
      (node (ref "JP5") (pin "11") (pinfunction "11_11") (pintype "passive"))
      (node (ref "JP5") (pin "12") (pinfunction "12_12") (pintype "passive"))
    )
    (net (code "98") (name "Net-(JP5-Pad13)") (class "Default")
      (node (ref "JP5") (pin "13") (pinfunction "13_13") (pintype "passive"))
      (node (ref "JP5") (pin "14") (pinfunction "14_14") (pintype "passive"))
    )
    (net (code "99") (name "Net-(JP5-Pad15)") (class "Default")
      (node (ref "JP5") (pin "15") (pinfunction "15_15") (pintype "passive"))
      (node (ref "JP5") (pin "16") (pinfunction "16_16") (pintype "passive"))
    )
    (net (code "100") (name "Net-(JP5-Pad17)") (class "Default")
      (node (ref "JP5") (pin "17") (pinfunction "17_17") (pintype "passive"))
      (node (ref "JP5") (pin "18") (pinfunction "18_18") (pintype "passive"))
    )
    (net (code "101") (name "Net-(JP5-Pad19)") (class "Default")
      (node (ref "JP5") (pin "19") (pinfunction "19_19") (pintype "passive"))
      (node (ref "JP5") (pin "20") (pinfunction "20_20") (pintype "passive"))
    )
    (net (code "102") (name "Net-(JP5-Pad21)") (class "Default")
      (node (ref "JP5") (pin "21") (pinfunction "21_21") (pintype "passive"))
      (node (ref "JP5") (pin "22") (pinfunction "22_22") (pintype "passive"))
    )
    (net (code "103") (name "Net-(JP5-Pad27)") (class "Default")
      (node (ref "JP5") (pin "27") (pinfunction "27_27") (pintype "passive"))
      (node (ref "JP5") (pin "28") (pinfunction "28_28") (pintype "passive"))
    )
    (net (code "104") (name "Net-(JP5-Pad29)") (class "Default")
      (node (ref "JP5") (pin "29") (pinfunction "29_29") (pintype "passive"))
      (node (ref "JP5") (pin "30") (pinfunction "30_30") (pintype "passive"))
    )
    (net (code "105") (name "Net-(JP6-Pad5)") (class "Default")
      (node (ref "JP6") (pin "5") (pinfunction "5_5") (pintype "passive"))
      (node (ref "JP6") (pin "6") (pinfunction "6_6") (pintype "passive"))
    )
    (net (code "106") (name "Net-(JP6-Pad7)") (class "Default")
      (node (ref "JP6") (pin "7") (pinfunction "7_7") (pintype "passive"))
      (node (ref "JP6") (pin "8") (pinfunction "8_8") (pintype "passive"))
    )
    (net (code "107") (name "Net-(JP6-Pad10)") (class "Default")
      (node (ref "JP6") (pin "10") (pinfunction "10_10") (pintype "passive"))
      (node (ref "JP6") (pin "9") (pinfunction "9_9") (pintype "passive"))
    )
    (net (code "108") (name "Net-(JP6-Pad11)") (class "Default")
      (node (ref "JP6") (pin "11") (pinfunction "11_11") (pintype "passive"))
      (node (ref "JP6") (pin "12") (pinfunction "12_12") (pintype "passive"))
    )
    (net (code "109") (name "Net-(JP6-Pad25)") (class "Default")
      (node (ref "JP6") (pin "25") (pinfunction "25_25") (pintype "passive"))
      (node (ref "JP6") (pin "26") (pinfunction "26_26") (pintype "passive"))
    )
    (net (code "110") (name "Net-(JP6-Pad27)") (class "Default")
      (node (ref "JP6") (pin "27") (pinfunction "27_27") (pintype "passive"))
      (node (ref "JP6") (pin "28") (pinfunction "28_28") (pintype "passive"))
    )
    (net (code "111") (name "Net-(JP6-Pad29)") (class "Default")
      (node (ref "JP6") (pin "29") (pinfunction "29_29") (pintype "passive"))
      (node (ref "JP6") (pin "30") (pinfunction "30_30") (pintype "passive"))
    )
    (net (code "112") (name "Net-(LED1-PadA)") (class "Default")
      (node (ref "LED1") (pin "A") (pinfunction "A_A") (pintype "passive"))
      (node (ref "R1") (pin "2") (pinfunction "2_2") (pintype "passive"))
    )
    (net (code "113") (name "Net-(LED2-PadA)") (class "Default")
      (node (ref "LED2") (pin "A") (pinfunction "A_A") (pintype "passive"))
      (node (ref "R2") (pin "2") (pinfunction "2_2") (pintype "passive"))
    )
    (net (code "114") (name "Net-(LED3-PadA)") (class "Default")
      (node (ref "LED3") (pin "A") (pinfunction "A_A") (pintype "passive"))
      (node (ref "R3") (pin "2") (pinfunction "2_2") (pintype "passive"))
    )
    (net (code "115") (name "Net-(LED4-PadA)") (class "Default")
      (node (ref "LED4") (pin "A") (pinfunction "A_A") (pintype "passive"))
      (node (ref "R4") (pin "2") (pinfunction "2_2") (pintype "passive"))
    )
    (net (code "116") (name "Net-(LED5-PadA)") (class "Default")
      (node (ref "LED5") (pin "A") (pinfunction "A_A") (pintype "passive"))
      (node (ref "R5") (pin "2") (pinfunction "2_2") (pintype "passive"))
    )
    (net (code "117") (name "Net-(LED6-PadA)") (class "Default")
      (node (ref "LED6") (pin "A") (pinfunction "A_A") (pintype "passive"))
      (node (ref "R6") (pin "2") (pinfunction "2_2") (pintype "passive"))
    )
    (net (code "118") (name "Net-(LED7-PadA)") (class "Default")
      (node (ref "LED7") (pin "A") (pinfunction "A_A") (pintype "passive"))
      (node (ref "R7") (pin "2") (pinfunction "2_2") (pintype "passive"))
    )
    (net (code "119") (name "Net-(U$5-S)") (class "Default")
      (node (ref "U$5") (pin "P$1") (pinfunction "S_P$1") (pintype "passive"))
      (node (ref "U1") (pin "1") (pinfunction "~{A}_1") (pintype "bidirectional"))
      (node (ref "U1") (pin "3") (pinfunction "A_3") (pintype "bidirectional"))
      (node (ref "U2") (pin "1") (pinfunction "~{A}_1") (pintype "bidirectional"))
      (node (ref "U2") (pin "3") (pinfunction "A_3") (pintype "bidirectional"))
      (node (ref "U3") (pin "1") (pinfunction "~{A}_1") (pintype "bidirectional"))
      (node (ref "U3") (pin "3") (pinfunction "A_3") (pintype "bidirectional"))
    )
    (net (code "120") (name "unconnected-(J1-Pad1)") (class "Default")
      (node (ref "J1") (pin "1") (pinfunction "1_1") (pintype "passive"))
    )
    (net (code "121") (name "unconnected-(J1-Pad4)") (class "Default")
      (node (ref "J1") (pin "4") (pinfunction "4_4") (pintype "passive"))
    )
    (net (code "122") (name "unconnected-(J1-Pad5)") (class "Default")
      (node (ref "J1") (pin "5") (pinfunction "5_5") (pintype "passive"))
    )
    (net (code "123") (name "unconnected-(J1-Pad7)") (class "Default")
      (node (ref "J1") (pin "7") (pinfunction "7_7") (pintype "passive"))
    )
    (net (code "124") (name "unconnected-(J1-Pad9)") (class "Default")
      (node (ref "J1") (pin "9") (pinfunction "9_9") (pintype "passive"))
    )
    (net (code "125") (name "unconnected-(J1-Pad10)") (class "Default")
      (node (ref "J1") (pin "10") (pinfunction "10_10") (pintype "passive"))
    )
    (net (code "126") (name "unconnected-(J2-Pad1)") (class "Default")
      (node (ref "J2") (pin "1") (pinfunction "1_1") (pintype "passive"))
    )
    (net (code "127") (name "unconnected-(J2-Pad4)") (class "Default")
      (node (ref "J2") (pin "4") (pinfunction "4_4") (pintype "passive"))
    )
    (net (code "128") (name "unconnected-(J2-Pad5)") (class "Default")
      (node (ref "J2") (pin "5") (pinfunction "5_5") (pintype "passive"))
    )
    (net (code "129") (name "unconnected-(J2-Pad7)") (class "Default")
      (node (ref "J2") (pin "7") (pinfunction "7_7") (pintype "passive"))
    )
    (net (code "130") (name "unconnected-(J2-Pad9)") (class "Default")
      (node (ref "J2") (pin "9") (pinfunction "9_9") (pintype "passive"))
    )
    (net (code "131") (name "unconnected-(J2-Pad10)") (class "Default")
      (node (ref "J2") (pin "10") (pinfunction "10_10") (pintype "passive"))
    )
    (net (code "132") (name "unconnected-(J3-Pad1)") (class "Default")
      (node (ref "J3") (pin "1") (pinfunction "1_1") (pintype "passive"))
    )
    (net (code "133") (name "unconnected-(J3-Pad4)") (class "Default")
      (node (ref "J3") (pin "4") (pinfunction "4_4") (pintype "passive"))
    )
    (net (code "134") (name "unconnected-(J3-Pad5)") (class "Default")
      (node (ref "J3") (pin "5") (pinfunction "5_5") (pintype "passive"))
    )
    (net (code "135") (name "unconnected-(J3-Pad7)") (class "Default")
      (node (ref "J3") (pin "7") (pinfunction "7_7") (pintype "passive"))
    )
    (net (code "136") (name "unconnected-(J3-Pad9)") (class "Default")
      (node (ref "J3") (pin "9") (pinfunction "9_9") (pintype "passive"))
    )
    (net (code "137") (name "unconnected-(J3-Pad10)") (class "Default")
      (node (ref "J3") (pin "10") (pinfunction "10_10") (pintype "passive"))
    )
    (net (code "138") (name "unconnected-(J4-Pad1)") (class "Default")
      (node (ref "J4") (pin "1") (pinfunction "1_1") (pintype "passive"))
    )
    (net (code "139") (name "unconnected-(J4-Pad4)") (class "Default")
      (node (ref "J4") (pin "4") (pinfunction "4_4") (pintype "passive"))
    )
    (net (code "140") (name "unconnected-(J4-Pad5)") (class "Default")
      (node (ref "J4") (pin "5") (pinfunction "5_5") (pintype "passive"))
    )
    (net (code "141") (name "unconnected-(J4-Pad7)") (class "Default")
      (node (ref "J4") (pin "7") (pinfunction "7_7") (pintype "passive"))
    )
    (net (code "142") (name "unconnected-(J4-Pad9)") (class "Default")
      (node (ref "J4") (pin "9") (pinfunction "9_9") (pintype "passive"))
    )
    (net (code "143") (name "unconnected-(J4-Pad10)") (class "Default")
      (node (ref "J4") (pin "10") (pinfunction "10_10") (pintype "passive"))
    )
    (net (code "144") (name "unconnected-(JP1-Pad2)") (class "Default")
      (node (ref "JP1") (pin "2") (pinfunction "2_2") (pintype "passive"))
    )
    (net (code "145") (name "unconnected-(JP1-Pad14)") (class "Default")
      (node (ref "JP1") (pin "14") (pinfunction "14_14") (pintype "passive"))
    )
    (net (code "146") (name "unconnected-(JP1-Pad24)") (class "Default")
      (node (ref "JP1") (pin "24") (pinfunction "24_24") (pintype "passive"))
    )
    (net (code "147") (name "unconnected-(JP1-Pad26)") (class "Default")
      (node (ref "JP1") (pin "26") (pinfunction "26_26") (pintype "passive"))
    )
    (net (code "148") (name "unconnected-(JP1-Pad28)") (class "Default")
      (node (ref "JP1") (pin "28") (pinfunction "28_28") (pintype "passive"))
    )
    (net (code "149") (name "unconnected-(JP1-Pad40)") (class "Default")
      (node (ref "JP1") (pin "40") (pinfunction "40_40") (pintype "passive"))
    )
    (net (code "150") (name "unconnected-(JP2-Pad1)") (class "Default")
      (node (ref "JP2") (pin "1") (pinfunction "1_1") (pintype "passive"))
    )
    (net (code "151") (name "unconnected-(JP2-Pad13)") (class "Default")
      (node (ref "JP2") (pin "13") (pinfunction "13_13") (pintype "passive"))
    )
    (net (code "152") (name "unconnected-(JP2-Pad17)") (class "Default")
      (node (ref "JP2") (pin "17") (pinfunction "17_17") (pintype "passive"))
    )
    (net (code "153") (name "unconnected-(JP2-Pad19)") (class "Default")
      (node (ref "JP2") (pin "19") (pinfunction "19_19") (pintype "passive"))
    )
    (net (code "154") (name "unconnected-(JP2-Pad27)") (class "Default")
      (node (ref "JP2") (pin "27") (pinfunction "27_27") (pintype "passive"))
    )
    (net (code "155") (name "unconnected-(JP2-Pad39)") (class "Default")
      (node (ref "JP2") (pin "39") (pinfunction "39_39") (pintype "passive"))
    )
  )
)
